# CPU.net
KiCad netlist of a schematic drawn in Altium Designer
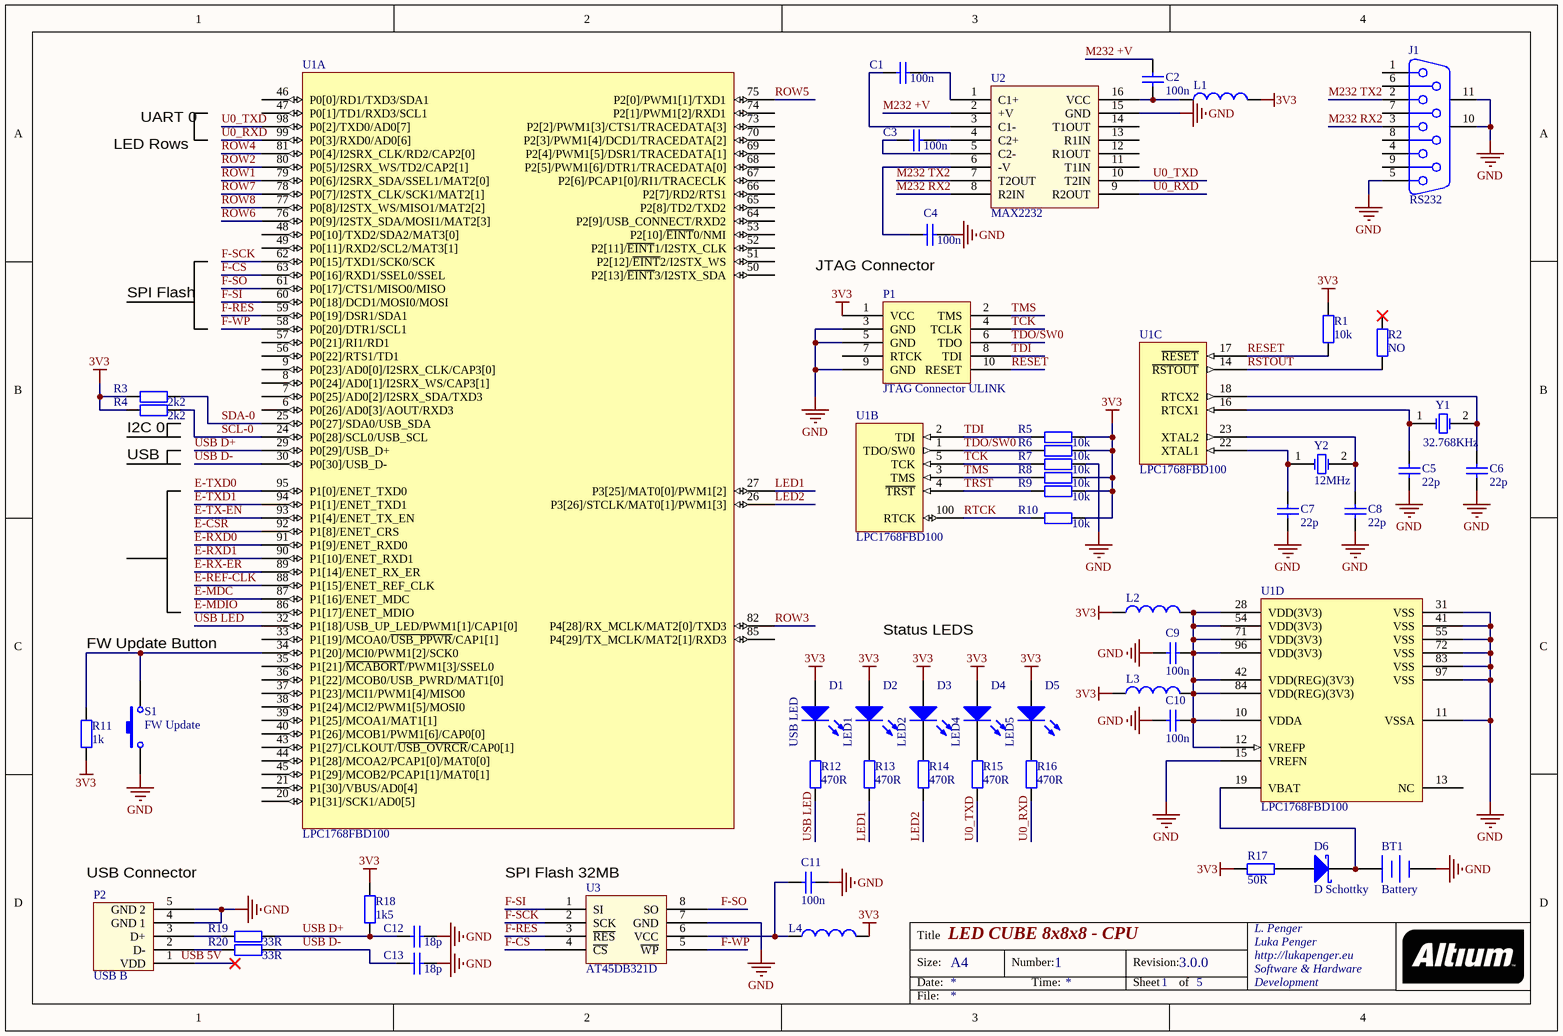
[diagram p0: CPU.SchDoc]

(export (version "E")
  (design (tool "Eeschema 10.0.6"))
  (components
    (comp (ref "BT1")
      (value "Battery")
      (footprint "Battery capacitor")
      (description "Multicell Battery")
      (fields (field (name "PUBLISHER") "Altium Limited"))
      (libsource (lib "Miscellaneous Devices") (part "Battery"))
    )
    (comp (ref "C1")
      (value "100n")
      (footprint "1608[0603]")
      (description "Capacitor")
      (fields (field (name "PUBLISHER") "Altium Limited"))
      (libsource (lib "Miscellaneous Devices") (part "Cap"))
    )
    (comp (ref "C2")
      (value "100n")
      (footprint "1608[0603]")
      (description "Capacitor")
      (fields (field (name "PUBLISHER") "Altium Limited"))
      (libsource (lib "Miscellaneous Devices") (part "Cap"))
    )
    (comp (ref "C3")
      (value "100n")
      (footprint "1608[0603]")
      (description "Capacitor")
      (fields (field (name "PUBLISHER") "Altium Limited"))
      (libsource (lib "Miscellaneous Devices") (part "Cap"))
    )
    (comp (ref "C4")
      (value "100n")
      (footprint "1608[0603]")
      (description "Capacitor")
      (fields (field (name "PUBLISHER") "Altium Limited"))
      (libsource (lib "Miscellaneous Devices") (part "Cap"))
    )
    (comp (ref "C5")
      (value "22p")
      (footprint "1608[0603]")
      (description "Capacitor")
      (fields (field (name "PUBLISHER") "Altium Limited"))
      (libsource (lib "Miscellaneous Devices") (part "Cap"))
    )
    (comp (ref "C6")
      (value "22p")
      (footprint "1608[0603]")
      (description "Capacitor")
      (fields (field (name "PUBLISHER") "Altium Limited"))
      (libsource (lib "Miscellaneous Devices") (part "Cap"))
    )
    (comp (ref "C7")
      (value "22p")
      (footprint "1608[0603]")
      (description "Capacitor")
      (fields (field (name "PUBLISHER") "Altium Limited"))
      (libsource (lib "Miscellaneous Devices") (part "Cap"))
    )
    (comp (ref "C8")
      (value "22p")
      (footprint "1608[0603]")
      (description "Capacitor")
      (fields (field (name "PUBLISHER") "Altium Limited"))
      (libsource (lib "Miscellaneous Devices") (part "Cap"))
    )
    (comp (ref "C9")
      (value "100n")
      (footprint "1608[0603]")
      (description "Capacitor")
      (fields (field (name "PUBLISHER") "Altium Limited"))
      (libsource (lib "Miscellaneous Devices") (part "Cap"))
    )
    (comp (ref "C10")
      (value "100n")
      (footprint "1608[0603]")
      (description "Capacitor")
      (fields (field (name "PUBLISHER") "Altium Limited"))
      (libsource (lib "Miscellaneous Devices") (part "Cap"))
    )
    (comp (ref "C11")
      (value "100n")
      (footprint "1608[0603]")
      (description "Capacitor")
      (fields (field (name "PUBLISHER") "Altium Limited"))
      (libsource (lib "Miscellaneous Devices") (part "Cap"))
    )
    (comp (ref "C12")
      (value "18p")
      (footprint "1608[0603]")
      (description "Capacitor")
      (fields (field (name "PUBLISHER") "Altium Limited"))
      (libsource (lib "Miscellaneous Devices") (part "Cap"))
    )
    (comp (ref "C13")
      (value "18p")
      (footprint "1608[0603]")
      (description "Capacitor")
      (fields (field (name "PUBLISHER") "Altium Limited"))
      (libsource (lib "Miscellaneous Devices") (part "Cap"))
    )
    (comp (ref "D1")
      (value "USB LED")
      (footprint "LED-1")
      (description "Typical INFRARED GaAs LED")
      (fields (field (name "PUBLISHER") "Altium Limited"))
      (libsource (lib "Miscellaneous Devices") (part "LED0"))
    )
    (comp (ref "D2")
      (value "LED1")
      (footprint "LED-1")
      (description "Typical INFRARED GaAs LED")
      (fields (field (name "PUBLISHER") "Altium Limited"))
      (libsource (lib "Miscellaneous Devices") (part "LED0"))
    )
    (comp (ref "D3")
      (value "LED2")
      (footprint "LED-1")
      (description "Typical INFRARED GaAs LED")
      (fields (field (name "PUBLISHER") "Altium Limited"))
      (libsource (lib "Miscellaneous Devices") (part "LED0"))
    )
    (comp (ref "D4")
      (value "LED4")
      (footprint "LED-1")
      (description "Typical INFRARED GaAs LED")
      (fields (field (name "PUBLISHER") "Altium Limited"))
      (libsource (lib "Miscellaneous Devices") (part "LED0"))
    )
    (comp (ref "D5")
      (value "LED5")
      (footprint "LED-1")
      (description "Typical INFRARED GaAs LED")
      (fields (field (name "PUBLISHER") "Altium Limited"))
      (libsource (lib "Miscellaneous Devices") (part "LED0"))
    )
    (comp (ref "D6")
      (value "D Schottky")
      (footprint "SMB")
      (description "Schottky Diode")
      (fields (field (name "PUBLISHER") "Altium Limited"))
      (libsource (lib "Miscellaneous Devices") (part "D Schottky"))
    )
    (comp (ref "J1")
      (value "RS232")
      (footprint "DSUB1.385-2H9")
      (description "Receptacle Assembly, 9 Position, Right Angle")
      (fields (field (name "PUBLISHER") "Altium Limited"))
      (libsource (lib "Miscellaneous Connectors") (part "D Connector 9"))
    )
    (comp (ref "L1")
      (value "Inductor")
      (footprint "1608[0603]")
      (fields (field (name "PUBLISHER") "Altium Limited"))
      (libsource (lib "Miscellaneous Devices") (part "Inductor"))
    )
    (comp (ref "L2")
      (value "Inductor")
      (footprint "1608[0603]")
      (fields (field (name "PUBLISHER") "Altium Limited"))
      (libsource (lib "Miscellaneous Devices") (part "Inductor"))
    )
    (comp (ref "L3")
      (value "Inductor")
      (footprint "1608[0603]")
      (fields (field (name "PUBLISHER") "Altium Limited"))
      (libsource (lib "Miscellaneous Devices") (part "Inductor"))
    )
    (comp (ref "L4")
      (value "Inductor")
      (footprint "1608[0603]")
      (fields (field (name "PUBLISHER") "Altium Limited"))
      (libsource (lib "Miscellaneous Devices") (part "Inductor"))
    )
    (comp (ref "P1")
      (value "JTAG Connector ULINK")
      (footprint "JTAG Connector ULINK")
      (description "JTAG Connector")
      (libsource (lib "LP_Lib") (part "JTAG Connector ULINK"))
    )
    (comp (ref "P2")
      (value "USB B")
      (footprint "USB B")
      (description "USB Connector")
      (libsource (lib "LP_Lib") (part "USB B"))
    )
    (comp (ref "R1")
      (value "10k")
      (footprint "1608[0603]")
      (description "Resistor")
      (fields (field (name "PUBLISHER") "Altium Limited"))
      (libsource (lib "") (part "Res2_1"))
    )
    (comp (ref "R2")
      (value "NO")
      (footprint "1608[0603]")
      (description "Resistor")
      (fields (field (name "PUBLISHER") "Altium Limited"))
      (libsource (lib "") (part "Res2_1"))
    )
    (comp (ref "R3")
      (value "2k2")
      (footprint "1608[0603]")
      (description "Resistor")
      (fields (field (name "PUBLISHER") "Altium Limited"))
      (libsource (lib "Miscellaneous Devices") (part "Res2"))
    )
    (comp (ref "R4")
      (value "2k2")
      (footprint "1608[0603]")
      (description "Resistor")
      (fields (field (name "PUBLISHER") "Altium Limited"))
      (libsource (lib "Miscellaneous Devices") (part "Res2"))
    )
    (comp (ref "R5")
      (value "10k")
      (footprint "1608[0603]")
      (description "Resistor")
      (fields (field (name "PUBLISHER") "Altium Limited"))
      (libsource (lib "Miscellaneous Devices") (part "Res2"))
    )
    (comp (ref "R6")
      (value "10k")
      (footprint "1608[0603]")
      (description "Resistor")
      (fields (field (name "PUBLISHER") "Altium Limited"))
      (libsource (lib "Miscellaneous Devices") (part "Res2"))
    )
    (comp (ref "R7")
      (value "10k")
      (footprint "1608[0603]")
      (description "Resistor")
      (fields (field (name "PUBLISHER") "Altium Limited"))
      (libsource (lib "Miscellaneous Devices") (part "Res2"))
    )
    (comp (ref "R8")
      (value "10k")
      (footprint "1608[0603]")
      (description "Resistor")
      (fields (field (name "PUBLISHER") "Altium Limited"))
      (libsource (lib "Miscellaneous Devices") (part "Res2"))
    )
    (comp (ref "R9")
      (value "10k")
      (footprint "1608[0603]")
      (description "Resistor")
      (fields (field (name "PUBLISHER") "Altium Limited"))
      (libsource (lib "Miscellaneous Devices") (part "Res2"))
    )
    (comp (ref "R10")
      (value "10k")
      (footprint "1608[0603]")
      (description "Resistor")
      (fields (field (name "PUBLISHER") "Altium Limited"))
      (libsource (lib "Miscellaneous Devices") (part "Res2"))
    )
    (comp (ref "R11")
      (value "1k")
      (footprint "1608[0603]")
      (description "Resistor")
      (fields (field (name "PUBLISHER") "Altium Limited"))
      (libsource (lib "") (part "Res2_1"))
    )
    (comp (ref "R12")
      (value "470R")
      (footprint "1608[0603]")
      (description "Resistor")
      (fields (field (name "PUBLISHER") "Altium Limited"))
      (libsource (lib "") (part "Res2_1"))
    )
    (comp (ref "R13")
      (value "470R")
      (footprint "1608[0603]")
      (description "Resistor")
      (fields (field (name "PUBLISHER") "Altium Limited"))
      (libsource (lib "") (part "Res2_1"))
    )
    (comp (ref "R14")
      (value "470R")
      (footprint "1608[0603]")
      (description "Resistor")
      (fields (field (name "PUBLISHER") "Altium Limited"))
      (libsource (lib "") (part "Res2_1"))
    )
    (comp (ref "R15")
      (value "470R")
      (footprint "1608[0603]")
      (description "Resistor")
      (fields (field (name "PUBLISHER") "Altium Limited"))
      (libsource (lib "") (part "Res2_1"))
    )
    (comp (ref "R16")
      (value "470R")
      (footprint "1608[0603]")
      (description "Resistor")
      (fields (field (name "PUBLISHER") "Altium Limited"))
      (libsource (lib "") (part "Res2_1"))
    )
    (comp (ref "R17")
      (value "50R")
      (footprint "6-0805_N")
      (description "Resistor")
      (fields (field (name "PUBLISHER") "Altium Limited"))
      (libsource (lib "") (part "Res2_3"))
    )
    (comp (ref "R18")
      (value "1k5")
      (footprint "1608[0603]")
      (description "Resistor")
      (fields (field (name "PUBLISHER") "Altium Limited"))
      (libsource (lib "") (part "Res2_2"))
    )
    (comp (ref "R19")
      (value "33R")
      (footprint "1608[0603]")
      (description "Resistor")
      (fields (field (name "PUBLISHER") "Altium Limited"))
      (libsource (lib "") (part "Res2_3"))
    )
    (comp (ref "R20")
      (value "33R")
      (footprint "1608[0603]")
      (description "Resistor")
      (fields (field (name "PUBLISHER") "Altium Limited"))
      (libsource (lib "") (part "Res2_3"))
    )
    (comp (ref "S1")
      (value "FW Update")
      (footprint "SWITCH-TACTILE-90")
      (description "Switch")
      (fields (field (name "PUBLISHER") "Altium Limited"))
      (libsource (lib "Miscellaneous Devices") (part "SW-PB"))
    )
    (comp (ref "U1")
      (value "LPC1768FBD100")
      (footprint "SOT407-1_N")
      (fields (field (name "PUBLISHER") "Altium Limited"))
      (libsource (lib "") (part "LPC1768FBD100_1"))
    )
    (comp (ref "U2")
      (value "MAX2232")
      (footprint "SOIC16_N")
      (description "Dual 232 +3V3")
      (libsource (lib "LP_Lib") (part "MAX2232"))
    )
    (comp (ref "U3")
      (value "AT45DB321D")
      (footprint "AT45DB321D")
      (description "SPI Flash 32MB")
      (libsource (lib "LP_Lib") (part "AT45DB321D"))
    )
    (comp (ref "Y1")
      (value "32.768KHz")
      (footprint "Crystal 4.1x1.5")
      (description "Crystal Oscillator")
      (fields (field (name "PUBLISHER") "Altium Limited"))
      (libsource (lib "Miscellaneous Devices") (part "XTAL"))
    )
    (comp (ref "Y2")
      (value "12MHz")
      (footprint "5x3.2 Crystal")
      (description "Crystal Oscillator")
      (fields (field (name "PUBLISHER") "Altium Limited"))
      (libsource (lib "Miscellaneous Devices") (part "XTAL"))
    )
  )
  (nets
    (net (code "1") (name "/E-CSR") (class "Default")
      (node (ref "U1") (pin "92") (pinfunction "P1[8]/ENET_CRS_92") (pintype "bidirectional"))
    )
    (net (code "2") (name "/E-MDC") (class "Default")
      (node (ref "U1") (pin "87") (pinfunction "P1[16]/ENET_MDC_87") (pintype "bidirectional"))
    )
    (net (code "3") (name "/E-MDIO") (class "Default")
      (node (ref "U1") (pin "86") (pinfunction "P1[17]/ENET_MDIO_86") (pintype "bidirectional"))
    )
    (net (code "4") (name "/E-REF-CLK") (class "Default")
      (node (ref "U1") (pin "88") (pinfunction "P1[15]/ENET_REF_CLK_88") (pintype "bidirectional"))
    )
    (net (code "5") (name "/E-RX-ER") (class "Default")
      (node (ref "U1") (pin "89") (pinfunction "P1[14]/ENET_RX_ER_89") (pintype "bidirectional"))
    )
    (net (code "6") (name "/E-RXD0") (class "Default")
      (node (ref "U1") (pin "91") (pinfunction "P1[9]/ENET_RXD0_91") (pintype "bidirectional"))
    )
    (net (code "7") (name "/E-RXD1") (class "Default")
      (node (ref "U1") (pin "90") (pinfunction "P1[10]/ENET_RXD1_90") (pintype "bidirectional"))
    )
    (net (code "8") (name "/E-TX-EN") (class "Default")
      (node (ref "U1") (pin "93") (pinfunction "P1[4]/ENET_TX_EN_93") (pintype "bidirectional"))
    )
    (net (code "9") (name "/E-TXD0") (class "Default")
      (node (ref "U1") (pin "95") (pinfunction "P1[0]/ENET_TXD0_95") (pintype "bidirectional"))
    )
    (net (code "10") (name "/E-TXD1") (class "Default")
      (node (ref "U1") (pin "94") (pinfunction "P1[1]/ENET_TXD1_94") (pintype "bidirectional"))
    )
    (net (code "11") (name "/F-CS") (class "Default")
      (node (ref "U1") (pin "63") (pinfunction "P0[16]/RXD1/SSEL0/SSEL_63") (pintype "bidirectional"))
      (node (ref "U3") (pin "4") (pinfunction "~{CS}_4") (pintype "passive"))
    )
    (net (code "12") (name "/F-RES") (class "Default")
      (node (ref "U1") (pin "59") (pinfunction "P0[19]/DSR1/SDA1_59") (pintype "bidirectional"))
      (node (ref "U3") (pin "3") (pinfunction "~{RES}_3") (pintype "passive"))
    )
    (net (code "13") (name "/F-SCK") (class "Default")
      (node (ref "U1") (pin "62") (pinfunction "P0[15]/TXD1/SCK0/SCK_62") (pintype "bidirectional"))
      (node (ref "U3") (pin "2") (pinfunction "SCK_2") (pintype "passive"))
    )
    (net (code "14") (name "/F-SI") (class "Default")
      (node (ref "U1") (pin "60") (pinfunction "P0[18]/DCD1/MOSI0/MOSI_60") (pintype "bidirectional"))
      (node (ref "U3") (pin "1") (pinfunction "SI_1") (pintype "passive"))
    )
    (net (code "15") (name "/F-SO") (class "Default")
      (node (ref "U1") (pin "61") (pinfunction "P0[17]/CTS1/MISO0/MISO_61") (pintype "bidirectional"))
      (node (ref "U3") (pin "8") (pinfunction "SO_8") (pintype "passive"))
    )
    (net (code "16") (name "/F-WP") (class "Default")
      (node (ref "U1") (pin "58") (pinfunction "P0[20]/DTR1/SCL1_58") (pintype "bidirectional"))
      (node (ref "U3") (pin "5") (pinfunction "~{WP}_5") (pintype "passive"))
    )
    (net (code "17") (name "/LED1") (class "Default")
      (node (ref "R13") (pin "1") (pinfunction "1_1") (pintype "passive"))
      (node (ref "U1") (pin "27") (pinfunction "P3[25]/MAT0[0]/PWM1[2]_27") (pintype "bidirectional"))
    )
    (net (code "18") (name "/LED2") (class "Default")
      (node (ref "R14") (pin "1") (pinfunction "1_1") (pintype "passive"))
      (node (ref "U1") (pin "26") (pinfunction "P3[26]/STCLK/MAT0[1]/PWM1[3]_26") (pintype "bidirectional"))
    )
    (net (code "19") (name "/M232 +V") (class "Default")
      (node (ref "C2") (pin "1") (pinfunction "1_1") (pintype "passive"))
      (node (ref "U2") (pin "2") (pinfunction "+V_2") (pintype "passive"))
    )
    (net (code "20") (name "/M232 RX2") (class "Default")
      (node (ref "J1") (pin "3") (pinfunction "3_3") (pintype "passive"))
      (node (ref "U2") (pin "8") (pinfunction "R2IN_8") (pintype "passive"))
    )
    (net (code "21") (name "/M232 TX2") (class "Default")
      (node (ref "J1") (pin "2") (pinfunction "2_2") (pintype "passive"))
      (node (ref "U2") (pin "7") (pinfunction "T2OUT_7") (pintype "passive"))
    )
    (net (code "22") (name "/RESET") (class "Default")
      (node (ref "P1") (pin "10") (pinfunction "RESET_10") (pintype "passive"))
      (node (ref "R1") (pin "1") (pinfunction "1_1") (pintype "passive"))
      (node (ref "U1") (pin "17") (pinfunction "~{RESET}_17") (pintype "input"))
    )
    (net (code "23") (name "/ROW1") (class "Default")
      (node (ref "U1") (pin "79") (pinfunction "P0[6]/I2SRX_SDA/SSEL1/MAT2[0]_79") (pintype "bidirectional"))
    )
    (net (code "24") (name "/ROW2") (class "Default")
      (node (ref "U1") (pin "80") (pinfunction "P0[5]/I2SRX_WS/TD2/CAP2[1]_80") (pintype "bidirectional"))
    )
    (net (code "25") (name "/ROW3") (class "Default")
      (node (ref "U1") (pin "82") (pinfunction "P4[28]/RX_MCLK/MAT2[0]/TXD3_82") (pintype "bidirectional"))
    )
    (net (code "26") (name "/ROW4") (class "Default")
      (node (ref "U1") (pin "81") (pinfunction "P0[4]/I2SRX_CLK/RD2/CAP2[0]_81") (pintype "bidirectional"))
    )
    (net (code "27") (name "/ROW5") (class "Default")
      (node (ref "U1") (pin "75") (pinfunction "P2[0]/PWM1[1]/TXD1_75") (pintype "bidirectional"))
    )
    (net (code "28") (name "/ROW6") (class "Default")
      (node (ref "U1") (pin "76") (pinfunction "P0[9]/I2STX_SDA/MOSI1/MAT2[3]_76") (pintype "bidirectional"))
    )
    (net (code "29") (name "/ROW7") (class "Default")
      (node (ref "U1") (pin "78") (pinfunction "P0[7]/I2STX_CLK/SCK1/MAT2[1]_78") (pintype "bidirectional"))
    )
    (net (code "30") (name "/ROW8") (class "Default")
      (node (ref "U1") (pin "77") (pinfunction "P0[8]/I2STX_WS/MISO1/MAT2[2]_77") (pintype "bidirectional"))
    )
    (net (code "31") (name "/RSTOUT") (class "Default")
      (node (ref "R2") (pin "1") (pinfunction "1_1") (pintype "passive"))
      (node (ref "U1") (pin "14") (pinfunction "~{RSTOUT}_14") (pintype "output"))
    )
    (net (code "32") (name "/RTCK") (class "Default")
      (node (ref "R10") (pin "1") (pinfunction "1_1") (pintype "passive"))
      (node (ref "U1") (pin "100") (pinfunction "RTCK_100") (pintype "bidirectional"))
    )
    (net (code "33") (name "/SCL-0") (class "Default")
      (node (ref "R4") (pin "2") (pinfunction "2_2") (pintype "passive"))
      (node (ref "U1") (pin "24") (pinfunction "P0[28]/SCL0/USB_SCL_24") (pintype "bidirectional"))
    )
    (net (code "34") (name "/SDA-0") (class "Default")
      (node (ref "R3") (pin "2") (pinfunction "2_2") (pintype "passive"))
      (node (ref "U1") (pin "25") (pinfunction "P0[27]/SDA0/USB_SDA_25") (pintype "bidirectional"))
    )
    (net (code "35") (name "/TCK") (class "Default")
      (node (ref "P1") (pin "4") (pinfunction "TCLK_4") (pintype "passive"))
      (node (ref "R7") (pin "1") (pinfunction "1_1") (pintype "passive"))
      (node (ref "U1") (pin "5") (pinfunction "TCK_5") (pintype "input"))
    )
    (net (code "36") (name "/TDI") (class "Default")
      (node (ref "P1") (pin "8") (pinfunction "TDI_8") (pintype "passive"))
      (node (ref "R5") (pin "1") (pinfunction "1_1") (pintype "passive"))
      (node (ref "U1") (pin "2") (pinfunction "TDI_2") (pintype "input"))
    )
    (net (code "37") (name "/TDO{slash}SW0") (class "Default")
      (node (ref "P1") (pin "6") (pinfunction "TDO_6") (pintype "passive"))
      (node (ref "R6") (pin "1") (pinfunction "1_1") (pintype "passive"))
      (node (ref "U1") (pin "1") (pinfunction "TDO/SW0_1") (pintype "output"))
    )
    (net (code "38") (name "/TMS") (class "Default")
      (node (ref "P1") (pin "2") (pinfunction "TMS_2") (pintype "passive"))
      (node (ref "R8") (pin "1") (pinfunction "1_1") (pintype "passive"))
      (node (ref "U1") (pin "3") (pinfunction "TMS_3") (pintype "input"))
    )
    (net (code "39") (name "/TRST") (class "Default")
      (node (ref "R9") (pin "1") (pinfunction "1_1") (pintype "passive"))
      (node (ref "U1") (pin "4") (pinfunction "~{TRST}_4") (pintype "input"))
    )
    (net (code "40") (name "/U0_RXD") (class "Default")
      (node (ref "R16") (pin "1") (pinfunction "1_1") (pintype "passive"))
      (node (ref "U1") (pin "99") (pinfunction "P0[3]/RXD0/AD0[6]_99") (pintype "bidirectional"))
      (node (ref "U2") (pin "9") (pinfunction "R2OUT_9") (pintype "passive"))
    )
    (net (code "41") (name "/U0_TXD") (class "Default")
      (node (ref "R15") (pin "1") (pinfunction "1_1") (pintype "passive"))
      (node (ref "U1") (pin "98") (pinfunction "P0[2]/TXD0/AD0[7]_98") (pintype "bidirectional"))
      (node (ref "U2") (pin "10") (pinfunction "T2IN_10") (pintype "passive"))
    )
    (net (code "43") (name "/USB D+") (class "Default")
      (node (ref "C12") (pin "1") (pinfunction "1_1") (pintype "passive"))
      (node (ref "R18") (pin "2") (pinfunction "2_2") (pintype "passive"))
      (node (ref "R19") (pin "1") (pinfunction "1_1") (pintype "passive"))
      (node (ref "U1") (pin "29") (pinfunction "P0[29]/USB_D+_29") (pintype "bidirectional"))
    )
    (net (code "44") (name "/USB D-") (class "Default")
      (node (ref "C13") (pin "1") (pinfunction "1_1") (pintype "passive"))
      (node (ref "R20") (pin "1") (pinfunction "1_1") (pintype "passive"))
      (node (ref "U1") (pin "30") (pinfunction "P0[30]/USB_D-_30") (pintype "bidirectional"))
    )
    (net (code "45") (name "/USB LED") (class "Default")
      (node (ref "R12") (pin "1") (pinfunction "1_1") (pintype "passive"))
      (node (ref "U1") (pin "32") (pinfunction "P1[18]/USB_UP_LED/PWM1[1]/CAP1[0]_32") (pintype "bidirectional"))
    )
    (net (code "46") (name "3V3") (class "Default")
      (node (ref "D1") (pin "1") (pinfunction "A_1") (pintype "passive"))
      (node (ref "D2") (pin "1") (pinfunction "A_1") (pintype "passive"))
      (node (ref "D3") (pin "1") (pinfunction "A_1") (pintype "passive"))
      (node (ref "D4") (pin "1") (pinfunction "A_1") (pintype "passive"))
      (node (ref "D5") (pin "1") (pinfunction "A_1") (pintype "passive"))
      (node (ref "L1") (pin "2") (pinfunction "2_2") (pintype "passive"))
      (node (ref "L2") (pin "1") (pinfunction "1_1") (pintype "passive"))
      (node (ref "L3") (pin "1") (pinfunction "1_1") (pintype "passive"))
      (node (ref "L4") (pin "2") (pinfunction "2_2") (pintype "passive"))
      (node (ref "P1") (pin "1") (pinfunction "VCC_1") (pintype "passive"))
      (node (ref "R1") (pin "2") (pinfunction "2_2") (pintype "passive"))
      (node (ref "R10") (pin "2") (pinfunction "2_2") (pintype "passive"))
      (node (ref "R11") (pin "1") (pinfunction "1_1") (pintype "passive"))
      (node (ref "R17") (pin "2") (pinfunction "2_2") (pintype "passive"))
      (node (ref "R18") (pin "1") (pinfunction "1_1") (pintype "passive"))
      (node (ref "R3") (pin "1") (pinfunction "1_1") (pintype "passive"))
      (node (ref "R4") (pin "1") (pinfunction "1_1") (pintype "passive"))
      (node (ref "R5") (pin "2") (pinfunction "2_2") (pintype "passive"))
      (node (ref "R6") (pin "2") (pinfunction "2_2") (pintype "passive"))
      (node (ref "R8") (pin "2") (pinfunction "2_2") (pintype "passive"))
      (node (ref "R9") (pin "2") (pinfunction "2_2") (pintype "passive"))
    )
    (net (code "47") (name "GND") (class "Default")
      (node (ref "BT1") (pin "2") (pinfunction "-_2") (pintype "passive"))
      (node (ref "C10") (pin "1") (pinfunction "1_1") (pintype "passive"))
      (node (ref "C11") (pin "1") (pinfunction "1_1") (pintype "passive"))
      (node (ref "C12") (pin "2") (pinfunction "2_2") (pintype "passive"))
      (node (ref "C13") (pin "2") (pinfunction "2_2") (pintype "passive"))
      (node (ref "C4") (pin "1") (pinfunction "1_1") (pintype "passive"))
      (node (ref "C5") (pin "1") (pinfunction "1_1") (pintype "passive"))
      (node (ref "C6") (pin "1") (pinfunction "1_1") (pintype "passive"))
      (node (ref "C7") (pin "1") (pinfunction "1_1") (pintype "passive"))
      (node (ref "C8") (pin "1") (pinfunction "1_1") (pintype "passive"))
      (node (ref "C9") (pin "2") (pinfunction "2_2") (pintype "passive"))
      (node (ref "J1") (pin "10") (pinfunction "MH1_10") (pintype "passive"))
      (node (ref "J1") (pin "11") (pinfunction "MH2_11") (pintype "passive"))
      (node (ref "J1") (pin "5") (pinfunction "5_5") (pintype "passive"))
      (node (ref "P1") (pin "3") (pinfunction "GND_3") (pintype "passive"))
      (node (ref "P1") (pin "5") (pinfunction "GND_5") (pintype "passive"))
      (node (ref "P1") (pin "9") (pinfunction "GND_9") (pintype "passive"))
      (node (ref "P2") (pin "4") (pinfunction "GND_1_4") (pintype "passive"))
      (node (ref "P2") (pin "5") (pinfunction "GND_2_5") (pintype "passive"))
      (node (ref "R7") (pin "2") (pinfunction "2_2") (pintype "passive"))
      (node (ref "S1") (pin "1") (pinfunction "1_1") (pintype "passive"))
      (node (ref "U1") (pin "11") (pinfunction "VSSA_11") (pintype "power_in"))
      (node (ref "U1") (pin "15") (pinfunction "VREFN_15") (pintype "power_in"))
      (node (ref "U1") (pin "31") (pinfunction "VSS_31") (pintype "power_in"))
      (node (ref "U1") (pin "41") (pinfunction "VSS_41") (pintype "power_in"))
      (node (ref "U1") (pin "55") (pinfunction "VSS_55") (pintype "power_in"))
      (node (ref "U1") (pin "72") (pinfunction "VSS_72") (pintype "power_in"))
      (node (ref "U1") (pin "83") (pinfunction "VSS_83") (pintype "power_in"))
      (node (ref "U1") (pin "97") (pinfunction "VSS_97") (pintype "power_in"))
      (node (ref "U2") (pin "15") (pinfunction "GND_15") (pintype "passive"))
      (node (ref "U3") (pin "7") (pinfunction "GND_7") (pintype "passive"))
    )
    (net (code "48") (name "Net-(BT1-+)") (class "Default")
      (node (ref "BT1") (pin "1") (pinfunction "+_1") (pintype "passive"))
      (node (ref "D6") (pin "2") (pinfunction "K_2") (pintype "passive"))
      (node (ref "U1") (pin "19") (pinfunction "VBAT_19") (pintype "power_in"))
    )
    (net (code "49") (name "Net-(D1-K)") (class "Default")
      (node (ref "D1") (pin "2") (pinfunction "K_2") (pintype "passive"))
      (node (ref "R12") (pin "2") (pinfunction "2_2") (pintype "passive"))
    )
    (net (code "50") (name "Net-(D2-K)") (class "Default")
      (node (ref "D2") (pin "2") (pinfunction "K_2") (pintype "passive"))
      (node (ref "R13") (pin "2") (pinfunction "2_2") (pintype "passive"))
    )
    (net (code "51") (name "Net-(D3-K)") (class "Default")
      (node (ref "D3") (pin "2") (pinfunction "K_2") (pintype "passive"))
      (node (ref "R14") (pin "2") (pinfunction "2_2") (pintype "passive"))
    )
    (net (code "52") (name "Net-(D4-K)") (class "Default")
      (node (ref "D4") (pin "2") (pinfunction "K_2") (pintype "passive"))
      (node (ref "R15") (pin "2") (pinfunction "2_2") (pintype "passive"))
    )
    (net (code "53") (name "Net-(D5-K)") (class "Default")
      (node (ref "D5") (pin "2") (pinfunction "K_2") (pintype "passive"))
      (node (ref "R16") (pin "2") (pinfunction "2_2") (pintype "passive"))
    )
    (net (code "54") (name "Net-(D6-A)") (class "Default")
      (node (ref "D6") (pin "1") (pinfunction "A_1") (pintype "passive"))
      (node (ref "R17") (pin "1") (pinfunction "1_1") (pintype "passive"))
    )
    (net (code "55") (name "Net-(P2-D+)") (class "Default")
      (node (ref "P2") (pin "3") (pinfunction "D+_3") (pintype "passive"))
      (node (ref "R19") (pin "2") (pinfunction "2_2") (pintype "passive"))
    )
    (net (code "56") (name "Net-(P2-D-)") (class "Default")
      (node (ref "P2") (pin "2") (pinfunction "D-_2") (pintype "passive"))
      (node (ref "R20") (pin "2") (pinfunction "2_2") (pintype "passive"))
    )
    (net (code "57") (name "Net-(U1A-P1[20]{slash}MCI0{slash}PWM1[2]{slash}SCK0)") (class "Default")
      (node (ref "R11") (pin "2") (pinfunction "2_2") (pintype "passive"))
      (node (ref "S1") (pin "2") (pinfunction "2_2") (pintype "passive"))
      (node (ref "U1") (pin "34") (pinfunction "P1[20]/MCI0/PWM1[2]/SCK0_34") (pintype "bidirectional"))
    )
    (net (code "58") (name "Net-(U1C-RTCX1)") (class "Default")
      (node (ref "C5") (pin "2") (pinfunction "2_2") (pintype "passive"))
      (node (ref "U1") (pin "16") (pinfunction "RTCX1_16") (pintype "input"))
      (node (ref "Y1") (pin "1") (pinfunction "OSC1_1") (pintype "passive"))
    )
    (net (code "59") (name "Net-(U1C-RTCX2)") (class "Default")
      (node (ref "C6") (pin "2") (pinfunction "2_2") (pintype "passive"))
      (node (ref "U1") (pin "18") (pinfunction "RTCX2_18") (pintype "output"))
      (node (ref "Y1") (pin "2") (pinfunction "OSC2_2") (pintype "passive"))
    )
    (net (code "60") (name "Net-(U1C-XTAL1)") (class "Default")
      (node (ref "C7") (pin "2") (pinfunction "2_2") (pintype "passive"))
      (node (ref "U1") (pin "22") (pinfunction "XTAL1_22") (pintype "input"))
      (node (ref "Y2") (pin "1") (pinfunction "OSC1_1") (pintype "passive"))
    )
    (net (code "61") (name "Net-(U1C-XTAL2)") (class "Default")
      (node (ref "C8") (pin "2") (pinfunction "2_2") (pintype "passive"))
      (node (ref "U1") (pin "23") (pinfunction "XTAL2_23") (pintype "output"))
      (node (ref "Y2") (pin "2") (pinfunction "OSC2_2") (pintype "passive"))
    )
    (net (code "62") (name "Net-(U1D-VDDA)") (class "Default")
      (node (ref "C10") (pin "2") (pinfunction "2_2") (pintype "passive"))
      (node (ref "C9") (pin "1") (pinfunction "1_1") (pintype "passive"))
      (node (ref "L2") (pin "2") (pinfunction "2_2") (pintype "passive"))
      (node (ref "L3") (pin "2") (pinfunction "2_2") (pintype "passive"))
      (node (ref "U1") (pin "10") (pinfunction "VDDA_10") (pintype "power_in"))
      (node (ref "U1") (pin "12") (pinfunction "VREFP_12") (pintype "input"))
      (node (ref "U1") (pin "28") (pinfunction "VDD(3V3)_28") (pintype "power_in"))
      (node (ref "U1") (pin "42") (pinfunction "VDD(REG)(3V3)_42") (pintype "power_in"))
      (node (ref "U1") (pin "54") (pinfunction "VDD(3V3)_54") (pintype "power_in"))
      (node (ref "U1") (pin "71") (pinfunction "VDD(3V3)_71") (pintype "power_in"))
      (node (ref "U1") (pin "84") (pinfunction "VDD(REG)(3V3)_84") (pintype "power_in"))
      (node (ref "U1") (pin "96") (pinfunction "VDD(3V3)_96") (pintype "power_in"))
    )
    (net (code "63") (name "Net-(U2--V)") (class "Default")
      (node (ref "C4") (pin "2") (pinfunction "2_2") (pintype "passive"))
      (node (ref "U2") (pin "6") (pinfunction "-V_6") (pintype "passive"))
    )
    (net (code "64") (name "Net-(U2-C1+)") (class "Default")
      (node (ref "C1") (pin "2") (pinfunction "2_2") (pintype "passive"))
      (node (ref "U2") (pin "1") (pinfunction "C1+_1") (pintype "passive"))
    )
    (net (code "65") (name "Net-(U2-C1-)") (class "Default")
      (node (ref "C1") (pin "1") (pinfunction "1_1") (pintype "passive"))
      (node (ref "U2") (pin "3") (pinfunction "C1-_3") (pintype "passive"))
    )
    (net (code "66") (name "Net-(U2-C2+)") (class "Default")
      (node (ref "C3") (pin "2") (pinfunction "2_2") (pintype "passive"))
      (node (ref "U2") (pin "4") (pinfunction "C2+_4") (pintype "passive"))
    )
    (net (code "67") (name "Net-(U2-C2-)") (class "Default")
      (node (ref "C3") (pin "1") (pinfunction "1_1") (pintype "passive"))
      (node (ref "U2") (pin "5") (pinfunction "C2-_5") (pintype "passive"))
    )
    (net (code "68") (name "Net-(U2-VCC)") (class "Default")
      (node (ref "C2") (pin "2") (pinfunction "2_2") (pintype "passive"))
      (node (ref "L1") (pin "1") (pinfunction "1_1") (pintype "passive"))
      (node (ref "U2") (pin "16") (pinfunction "VCC_16") (pintype "passive"))
    )
    (net (code "69") (name "Net-(U3-VCC)") (class "Default")
      (node (ref "C11") (pin "2") (pinfunction "2_2") (pintype "passive"))
      (node (ref "L4") (pin "1") (pinfunction "1_1") (pintype "passive"))
      (node (ref "U3") (pin "6") (pinfunction "VCC_6") (pintype "passive"))
    )
    (net (code "70") (name "unconnected-(J1-Pad1)") (class "Default")
      (node (ref "J1") (pin "1") (pinfunction "1_1") (pintype "passive"))
    )
    (net (code "71") (name "unconnected-(J1-Pad4)") (class "Default")
      (node (ref "J1") (pin "4") (pinfunction "4_4") (pintype "passive"))
    )
    (net (code "72") (name "unconnected-(J1-Pad6)") (class "Default")
      (node (ref "J1") (pin "6") (pinfunction "6_6") (pintype "passive"))
    )
    (net (code "73") (name "unconnected-(J1-Pad7)") (class "Default")
      (node (ref "J1") (pin "7") (pinfunction "7_7") (pintype "passive"))
    )
    (net (code "74") (name "unconnected-(J1-Pad8)") (class "Default")
      (node (ref "J1") (pin "8") (pinfunction "8_8") (pintype "passive"))
    )
    (net (code "75") (name "unconnected-(J1-Pad9)") (class "Default")
      (node (ref "J1") (pin "9") (pinfunction "9_9") (pintype "passive"))
    )
    (net (code "76") (name "unconnected-(P1-RTCK-Pad7)") (class "Default")
      (node (ref "P1") (pin "7") (pinfunction "RTCK_7") (pintype "passive"))
    )
    (net (code "77") (name "unconnected-(P2-VDD-Pad1)") (class "Default")
      (node (ref "P2") (pin "1") (pinfunction "VDD_1") (pintype "passive+no_connect"))
    )
    (net (code "78") (name "unconnected-(R2-Pad2)") (class "Default")
      (node (ref "R2") (pin "2") (pinfunction "2_2") (pintype "passive+no_connect"))
    )
    (net (code "79") (name "unconnected-(U1A-P0[0]{slash}RD1{slash}TXD3{slash}SDA1-Pad46)") (class "Default")
      (node (ref "U1") (pin "46") (pinfunction "P0[0]/RD1/TXD3/SDA1_46") (pintype "bidirectional"))
    )
    (net (code "80") (name "unconnected-(U1A-P0[1]{slash}TD1{slash}RXD3{slash}SCL1-Pad47)") (class "Default")
      (node (ref "U1") (pin "47") (pinfunction "P0[1]/TD1/RXD3/SCL1_47") (pintype "bidirectional"))
    )
    (net (code "81") (name "unconnected-(U1A-P0[10]{slash}TXD2{slash}SDA2{slash}MAT3[0]-Pad48)") (class "Default")
      (node (ref "U1") (pin "48") (pinfunction "P0[10]/TXD2/SDA2/MAT3[0]_48") (pintype "bidirectional"))
    )
    (net (code "82") (name "unconnected-(U1A-P0[11]{slash}RXD2{slash}SCL2{slash}MAT3[1]-Pad49)") (class "Default")
      (node (ref "U1") (pin "49") (pinfunction "P0[11]/RXD2/SCL2/MAT3[1]_49") (pintype "bidirectional"))
    )
    (net (code "83") (name "unconnected-(U1A-P0[21]{slash}RI1{slash}RD1-Pad57)") (class "Default")
      (node (ref "U1") (pin "57") (pinfunction "P0[21]/RI1/RD1_57") (pintype "bidirectional"))
    )
    (net (code "84") (name "unconnected-(U1A-P0[22]{slash}RTS1{slash}TD1-Pad56)") (class "Default")
      (node (ref "U1") (pin "56") (pinfunction "P0[22]/RTS1/TD1_56") (pintype "bidirectional"))
    )
    (net (code "85") (name "unconnected-(U1A-P0[23]{slash}AD0[0]{slash}I2SRX_CLK{slash}CAP3[0]-Pad9)") (class "Default")
      (node (ref "U1") (pin "9") (pinfunction "P0[23]/AD0[0]/I2SRX_CLK/CAP3[0]_9") (pintype "bidirectional"))
    )
    (net (code "86") (name "unconnected-(U1A-P0[24]{slash}AD0[1]{slash}I2SRX_WS{slash}CAP3[1]-Pad8)") (class "Default")
      (node (ref "U1") (pin "8") (pinfunction "P0[24]/AD0[1]/I2SRX_WS/CAP3[1]_8") (pintype "bidirectional"))
    )
    (net (code "87") (name "unconnected-(U1A-P0[25]{slash}AD0[2]{slash}I2SRX_SDA{slash}TXD3-Pad7)") (class "Default")
      (node (ref "U1") (pin "7") (pinfunction "P0[25]/AD0[2]/I2SRX_SDA/TXD3_7") (pintype "bidirectional"))
    )
    (net (code "88") (name "unconnected-(U1A-P0[26]{slash}AD0[3]{slash}AOUT{slash}RXD3-Pad6)") (class "Default")
      (node (ref "U1") (pin "6") (pinfunction "P0[26]/AD0[3]/AOUT/RXD3_6") (pintype "bidirectional"))
    )
    (net (code "89") (name "unconnected-(U1A-P1[19]{slash}MCOA0{slash}~{USB_PPWR}{slash}CAP1[1]-Pad33)") (class "Default")
      (node (ref "U1") (pin "33") (pinfunction "P1[19]/MCOA0/~{USB_PPWR}/CAP1[1]_33") (pintype "bidirectional"))
    )
    (net (code "90") (name "unconnected-(U1A-P1[21]{slash}~{MCABORT}{slash}PWM1[3]{slash}SSEL0-Pad35)") (class "Default")
      (node (ref "U1") (pin "35") (pinfunction "P1[21]/~{MCABORT}/PWM1[3]/SSEL0_35") (pintype "bidirectional"))
    )
    (net (code "91") (name "unconnected-(U1A-P1[22]{slash}MCOB0{slash}USB_PWRD{slash}MAT1[0]-Pad36)") (class "Default")
      (node (ref "U1") (pin "36") (pinfunction "P1[22]/MCOB0/USB_PWRD/MAT1[0]_36") (pintype "bidirectional"))
    )
    (net (code "92") (name "unconnected-(U1A-P1[23]{slash}MCI1{slash}PWM1[4]{slash}MISO0-Pad37)") (class "Default")
      (node (ref "U1") (pin "37") (pinfunction "P1[23]/MCI1/PWM1[4]/MISO0_37") (pintype "bidirectional"))
    )
    (net (code "93") (name "unconnected-(U1A-P1[24]{slash}MCI2{slash}PWM1[5]{slash}MOSI0-Pad38)") (class "Default")
      (node (ref "U1") (pin "38") (pinfunction "P1[24]/MCI2/PWM1[5]/MOSI0_38") (pintype "bidirectional"))
    )
    (net (code "94") (name "unconnected-(U1A-P1[25]{slash}MCOA1{slash}MAT1[1]-Pad39)") (class "Default")
      (node (ref "U1") (pin "39") (pinfunction "P1[25]/MCOA1/MAT1[1]_39") (pintype "bidirectional"))
    )
    (net (code "95") (name "unconnected-(U1A-P1[26]{slash}MCOB1{slash}PWM1[6]{slash}CAP0[0]-Pad40)") (class "Default")
      (node (ref "U1") (pin "40") (pinfunction "P1[26]/MCOB1/PWM1[6]/CAP0[0]_40") (pintype "bidirectional"))
    )
    (net (code "96") (name "unconnected-(U1A-P1[27]{slash}CLKOUT{slash}~{USB_OVRCR}{slash}CAP0[1]-Pad43)") (class "Default")
      (node (ref "U1") (pin "43") (pinfunction "P1[27]/CLKOUT/~{USB_OVRCR}/CAP0[1]_43") (pintype "bidirectional"))
    )
    (net (code "97") (name "unconnected-(U1A-P1[28]{slash}MCOA2{slash}PCAP1[0]{slash}MAT0[0]-Pad44)") (class "Default")
      (node (ref "U1") (pin "44") (pinfunction "P1[28]/MCOA2/PCAP1[0]/MAT0[0]_44") (pintype "bidirectional"))
    )
    (net (code "98") (name "unconnected-(U1A-P1[29]{slash}MCOB2{slash}PCAP1[1]{slash}MAT0[1]-Pad45)") (class "Default")
      (node (ref "U1") (pin "45") (pinfunction "P1[29]/MCOB2/PCAP1[1]/MAT0[1]_45") (pintype "bidirectional"))
    )
    (net (code "99") (name "unconnected-(U1A-P1[30]{slash}VBUS{slash}AD0[4]-Pad21)") (class "Default")
      (node (ref "U1") (pin "21") (pinfunction "P1[30]/VBUS/AD0[4]_21") (pintype "bidirectional"))
    )
    (net (code "100") (name "unconnected-(U1A-P1[31]{slash}SCK1{slash}AD0[5]-Pad20)") (class "Default")
      (node (ref "U1") (pin "20") (pinfunction "P1[31]/SCK1/AD0[5]_20") (pintype "bidirectional"))
    )
    (net (code "101") (name "unconnected-(U1A-P2[1]{slash}PWM1[2]{slash}RXD1-Pad74)") (class "Default")
      (node (ref "U1") (pin "74") (pinfunction "P2[1]/PWM1[2]/RXD1_74") (pintype "bidirectional"))
    )
    (net (code "102") (name "unconnected-(U1A-P2[2]{slash}PWM1[3]{slash}CTS1{slash}TRACEDATA[3]-Pad73)") (class "Default")
      (node (ref "U1") (pin "73") (pinfunction "P2[2]/PWM1[3]/CTS1/TRACEDATA[3]_73") (pintype "bidirectional"))
    )
    (net (code "103") (name "unconnected-(U1A-P2[3]{slash}PWM1[4]{slash}DCD1{slash}TRACEDATA[2]-Pad70)") (class "Default")
      (node (ref "U1") (pin "70") (pinfunction "P2[3]/PWM1[4]/DCD1/TRACEDATA[2]_70") (pintype "bidirectional"))
    )
    (net (code "104") (name "unconnected-(U1A-P2[4]{slash}PWM1[5]{slash}DSR1{slash}TRACEDATA[1]-Pad69)") (class "Default")
      (node (ref "U1") (pin "69") (pinfunction "P2[4]/PWM1[5]/DSR1/TRACEDATA[1]_69") (pintype "bidirectional"))
    )
    (net (code "105") (name "unconnected-(U1A-P2[5]{slash}PWM1[6]{slash}DTR1{slash}TRACEDATA[0]-Pad68)") (class "Default")
      (node (ref "U1") (pin "68") (pinfunction "P2[5]/PWM1[6]/DTR1/TRACEDATA[0]_68") (pintype "bidirectional"))
    )
    (net (code "106") (name "unconnected-(U1A-P2[6]{slash}PCAP1[0]{slash}RI1{slash}TRACECLK-Pad67)") (class "Default")
      (node (ref "U1") (pin "67") (pinfunction "P2[6]/PCAP1[0]/RI1/TRACECLK_67") (pintype "bidirectional"))
    )
    (net (code "107") (name "unconnected-(U1A-P2[7]{slash}RD2{slash}RTS1-Pad66)") (class "Default")
      (node (ref "U1") (pin "66") (pinfunction "P2[7]/RD2/RTS1_66") (pintype "bidirectional"))
    )
    (net (code "108") (name "unconnected-(U1A-P2[8]{slash}TD2{slash}TXD2-Pad65)") (class "Default")
      (node (ref "U1") (pin "65") (pinfunction "P2[8]/TD2/TXD2_65") (pintype "bidirectional"))
    )
    (net (code "109") (name "unconnected-(U1A-P2[9]{slash}USB_CONNECT{slash}RXD2-Pad64)") (class "Default")
      (node (ref "U1") (pin "64") (pinfunction "P2[9]/USB_CONNECT/RXD2_64") (pintype "bidirectional"))
    )
    (net (code "110") (name "unconnected-(U1A-P2[10]{slash}~{EINT}0{slash}NMI-Pad53)") (class "Default")
      (node (ref "U1") (pin "53") (pinfunction "P2[10]/~{EINT}0/NMI_53") (pintype "bidirectional"))
    )
    (net (code "111") (name "unconnected-(U1A-P2[11]{slash}~{EINT}1{slash}I2STX_CLK-Pad52)") (class "Default")
      (node (ref "U1") (pin "52") (pinfunction "P2[11]/~{EINT}1/I2STX_CLK_52") (pintype "bidirectional"))
    )
    (net (code "112") (name "unconnected-(U1A-P2[12]{slash}~{EINT}2{slash}I2STX_WS-Pad51)") (class "Default")
      (node (ref "U1") (pin "51") (pinfunction "P2[12]/~{EINT}2/I2STX_WS_51") (pintype "bidirectional"))
    )
    (net (code "113") (name "unconnected-(U1A-P2[13]{slash}~{EINT}3{slash}I2STX_SDA-Pad50)") (class "Default")
      (node (ref "U1") (pin "50") (pinfunction "P2[13]/~{EINT}3/I2STX_SDA_50") (pintype "bidirectional"))
    )
    (net (code "114") (name "unconnected-(U1A-P4[29]{slash}TX_MCLK{slash}MAT2[1]{slash}RXD3-Pad85)") (class "Default")
      (node (ref "U1") (pin "85") (pinfunction "P4[29]/TX_MCLK/MAT2[1]/RXD3_85") (pintype "bidirectional"))
    )
    (net (code "115") (name "unconnected-(U1D-NC-Pad13)") (class "Default")
      (node (ref "U1") (pin "13") (pinfunction "NC_13") (pintype "power_in"))
    )
    (net (code "116") (name "unconnected-(U2-R1IN-Pad13)") (class "Default")
      (node (ref "U2") (pin "13") (pinfunction "R1IN_13") (pintype "passive"))
    )
    (net (code "117") (name "unconnected-(U2-R1OUT-Pad12)") (class "Default")
      (node (ref "U2") (pin "12") (pinfunction "R1OUT_12") (pintype "passive"))
    )
    (net (code "118") (name "unconnected-(U2-T1IN-Pad11)") (class "Default")
      (node (ref "U2") (pin "11") (pinfunction "T1IN_11") (pintype "passive"))
    )
    (net (code "119") (name "unconnected-(U2-T1OUT-Pad14)") (class "Default")
      (node (ref "U2") (pin "14") (pinfunction "T1OUT_14") (pintype "passive"))
    )
  )
)
